# embedded-gw.net
KiCad netlist of a schematic drawn in EAGLE
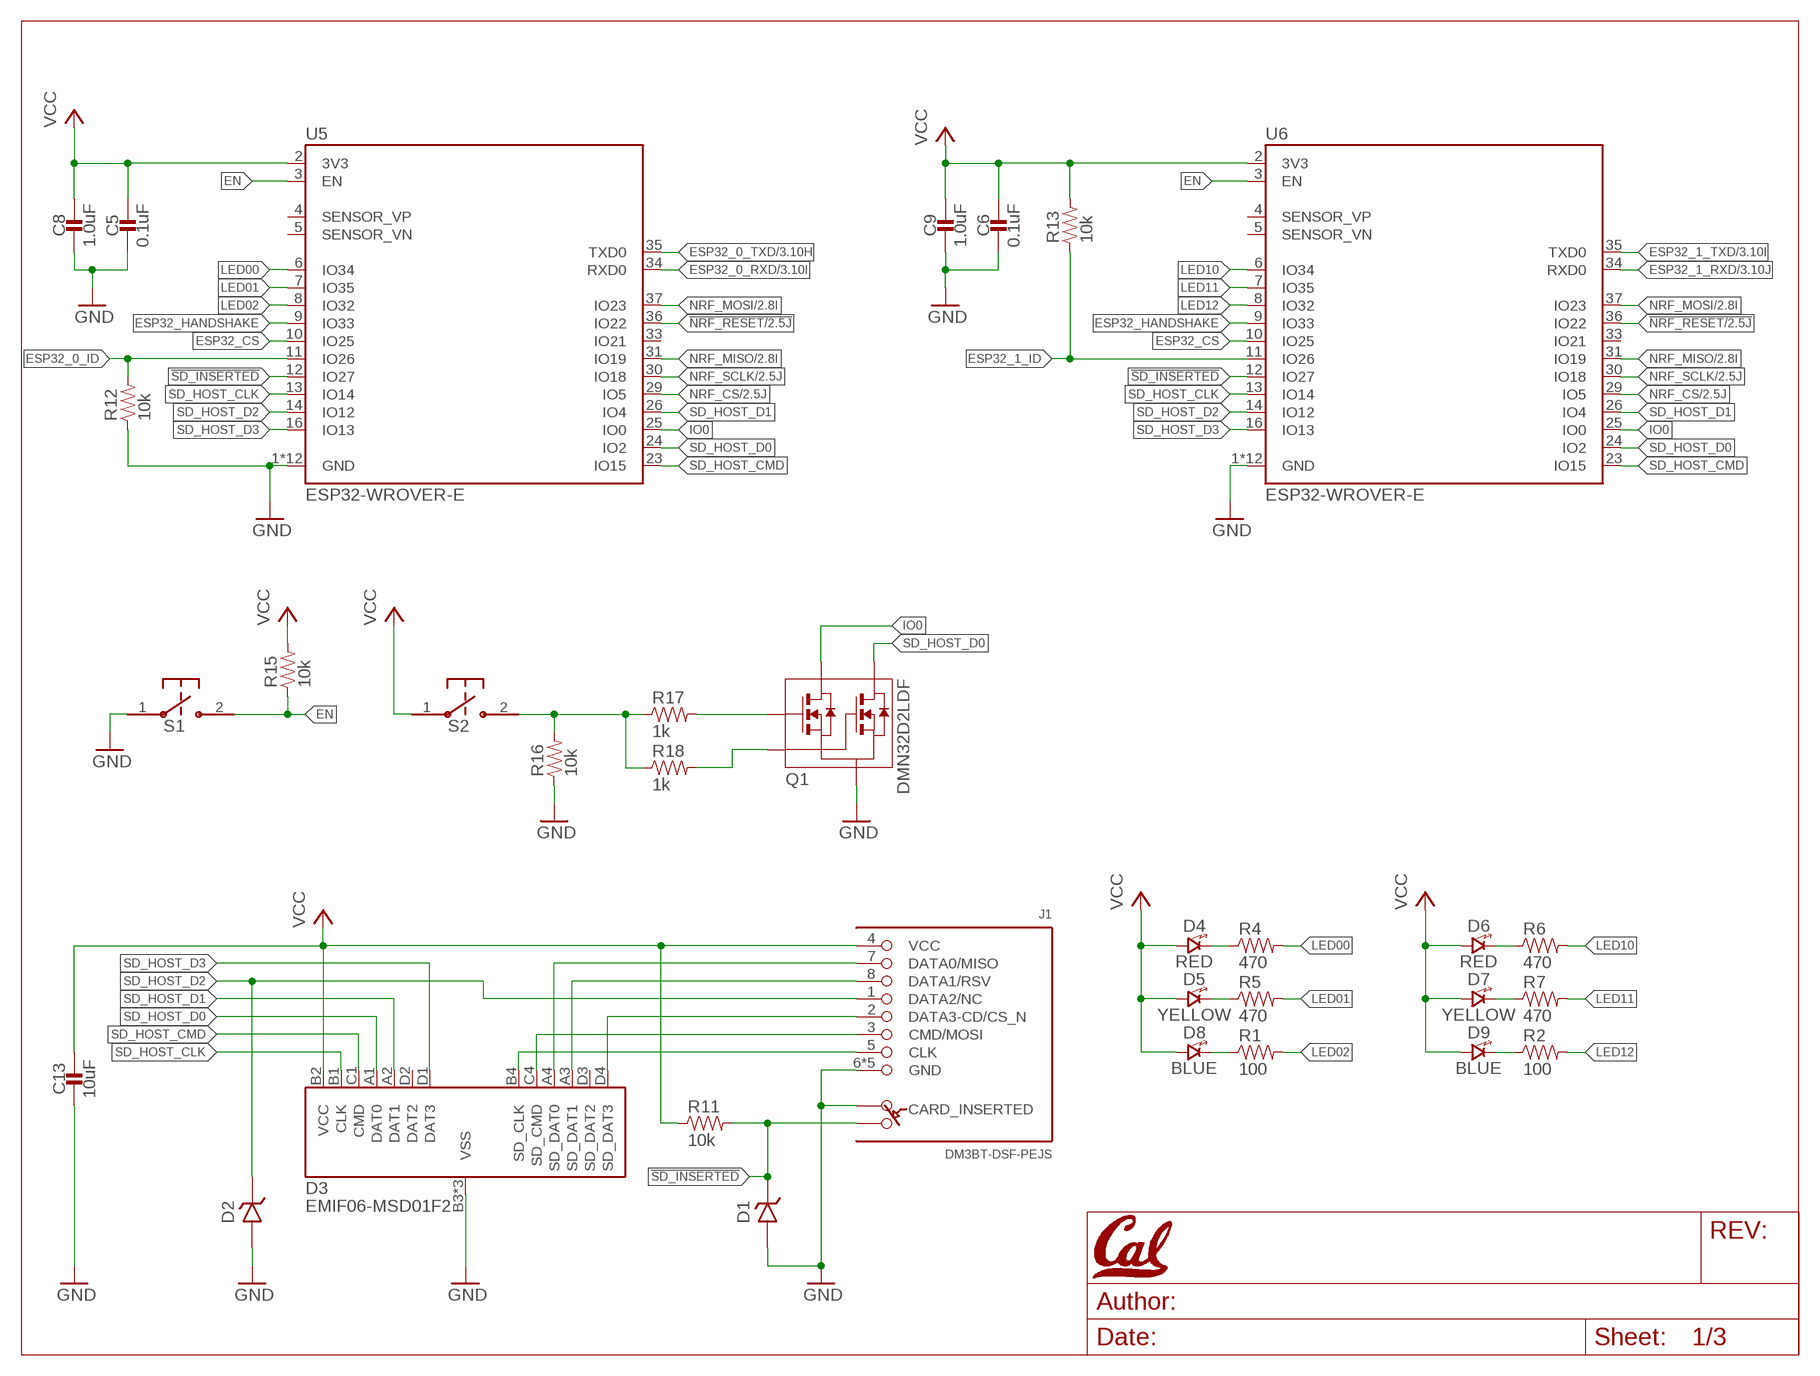
[diagram p0: schematic, sheet 1]
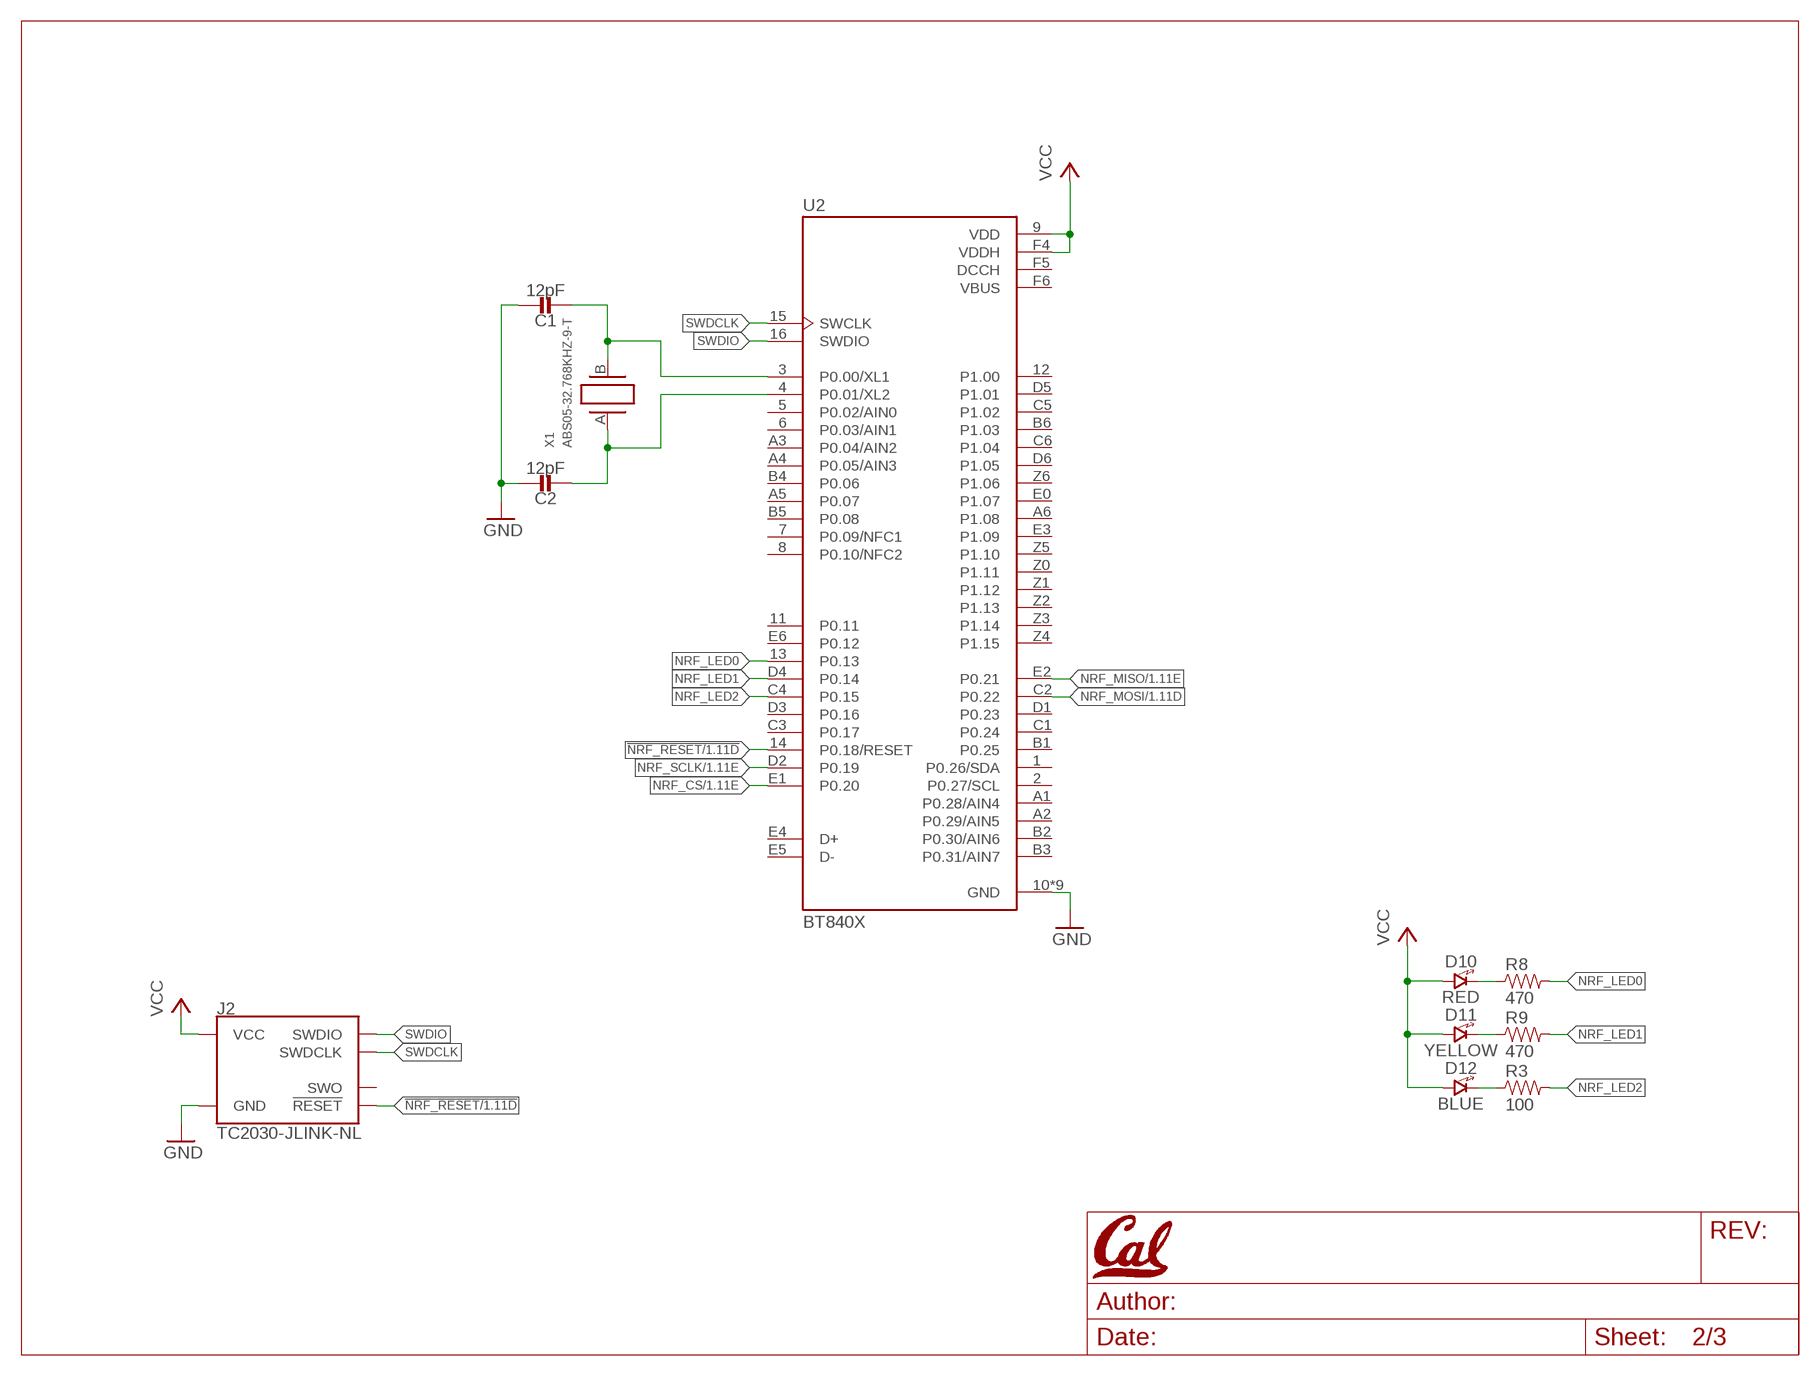
[diagram p1: schematic, sheet 2]
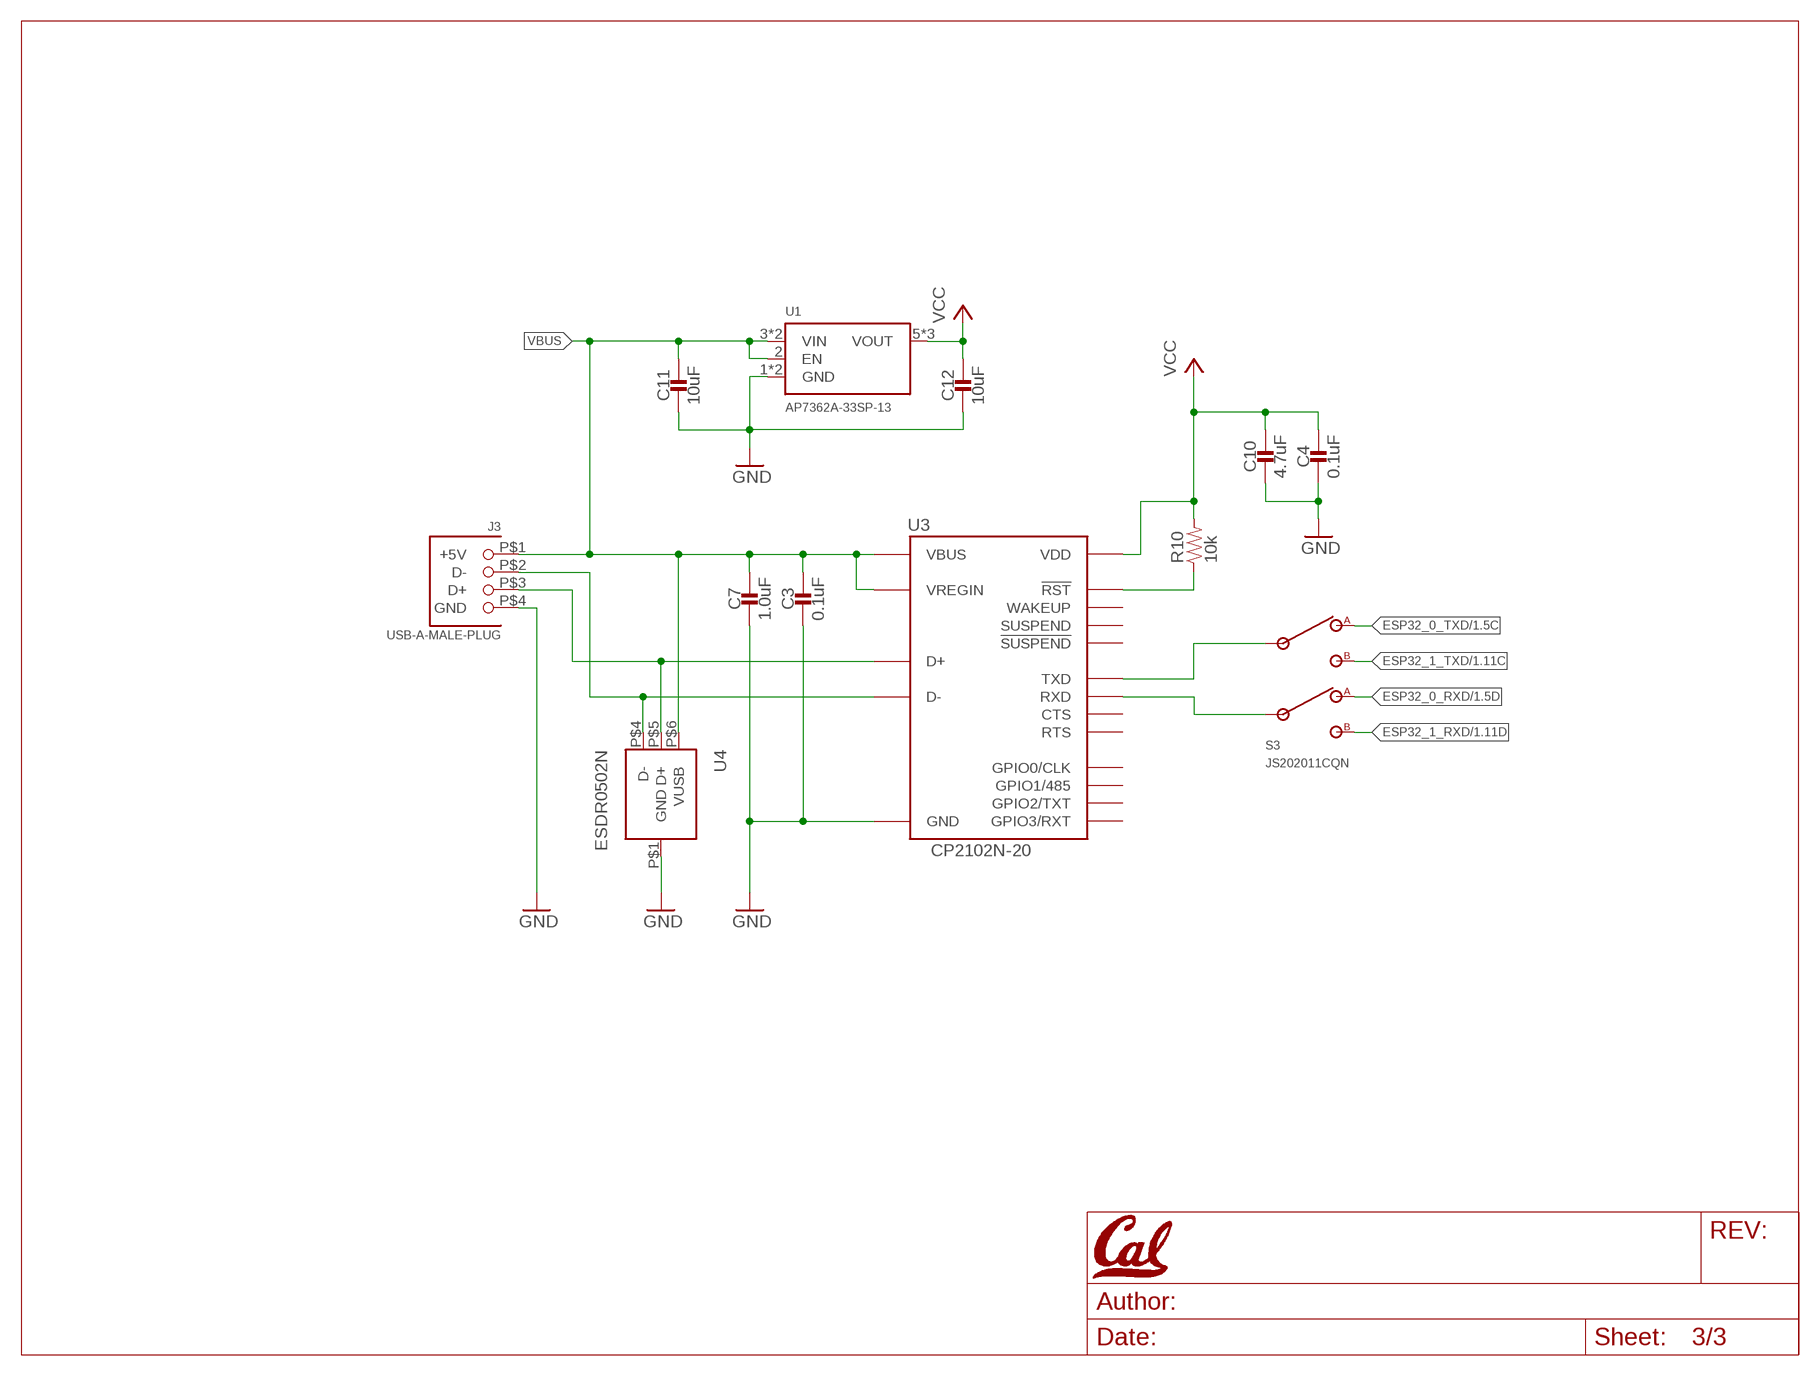
[diagram p2: schematic, sheet 3]

(export (version "E")
  (design (tool "Eeschema 10.0.6"))
  (components
    (comp (ref "C3")
      (value "0.1uF")
      (footprint "eagle-import:0402_CAP")
      (fields (field (name "MPN") "CL05B104KQ5NNNC"))
      (libsource (lib "eagle-import") (part "CAPACITOR0402_CAP"))
    )
    (comp (ref "C4")
      (value "0.1uF")
      (footprint "eagle-import:0402_CAP")
      (fields (field (name "MPN") "CL05B104KQ5NNNC"))
      (libsource (lib "eagle-import") (part "CAPACITOR0402_CAP"))
    )
    (comp (ref "C7")
      (value "1.0uF")
      (footprint "eagle-import:0402_CAP")
      (fields (field (name "MPN") "CL05A105KQ5NNNC"))
      (libsource (lib "eagle-import") (part "CAPACITOR0402_CAP"))
    )
    (comp (ref "C10")
      (value "4.7uF")
      (footprint "eagle-import:0603_CAP")
      (fields (field (name "MPN") "CL10A475KQ8NNNC"))
      (libsource (lib "eagle-import") (part "CAPACITOR0603_CAP"))
    )
    (comp (ref "C11")
      (value "10uF")
      (footprint "eagle-import:0805_CAP")
      (fields (field (name "MPN") "CL21A106KQCLNNC"))
      (libsource (lib "eagle-import") (part "CAPACITOR0805_CAP"))
    )
    (comp (ref "C12")
      (value "10uF")
      (footprint "eagle-import:0805_CAP")
      (fields (field (name "MPN") "CL21A106KQCLNNC"))
      (libsource (lib "eagle-import") (part "CAPACITOR0805_CAP"))
    )
    (comp (ref "J3")
      (value "USB-A-MALE-PLUG")
      (footprint "eagle-import:USB_A_MALE_PLUG_CUI_UP2-AH")
      (fields (field (name "MANUFACTURER") "CUI") (field (name "MPN") "UP2-AH-1-TH"))
      (libsource (lib "eagle-import") (part "USB-A-MALE-PLUG"))
    )
    (comp (ref "R10")
      (value "10k")
      (footprint "eagle-import:0402_RES")
      (fields (field (name "MPN") "RMCF0402JT10K0"))
      (libsource (lib "eagle-import") (part "RESISTOR0402_RES"))
    )
    (comp (ref "S3")
      (value "JS202011CQN")
      (footprint "eagle-import:JS202011CQN")
      (fields (field (name "MANUFACTURER") "C&K"))
      (libsource (lib "eagle-import") (part "JS202011CQN"))
    )
    (comp (ref "U1")
      (value "AP7362A-33SP-13")
      (footprint "eagle-import:SO-8EP")
      (fields (field (name "MANUFACTURER") "Diodes Incorporated") (field (name "MPN") "AP7362A-33SP-13 "))
      (libsource (lib "eagle-import") (part "AP7362A-33SP-13"))
    )
    (comp (ref "U3")
      (value "CP2102N-20")
      (footprint "eagle-import:QFN-20-3MM")
      (fields (field (name "MANUFACTURER") "SiLabs") (field (name "MPN") "CP2102N-A01-GQFN20"))
      (libsource (lib "eagle-import") (part "CP2102N-20"))
    )
    (comp (ref "U4")
      (value "ESDR0502N")
      (footprint "eagle-import:UDFN-6")
      (fields (field (name "MPN") "ESDR0502NMUTBG"))
      (libsource (lib "eagle-import") (part "ESDR0502N"))
    )
    (comp (ref "C5")
      (value "0.1uF")
      (footprint "eagle-import:0402_CAP")
      (fields (field (name "MPN") "CL05B104KQ5NNNC"))
      (libsource (lib "eagle-import") (part "CAPACITOR0402_CAP"))
    )
    (comp (ref "C6")
      (value "0.1uF")
      (footprint "eagle-import:0402_CAP")
      (fields (field (name "MPN") "CL05B104KQ5NNNC"))
      (libsource (lib "eagle-import") (part "CAPACITOR0402_CAP"))
    )
    (comp (ref "C8")
      (value "1.0uF")
      (footprint "eagle-import:0402_CAP")
      (fields (field (name "MPN") "CL05A105KQ5NNNC"))
      (libsource (lib "eagle-import") (part "CAPACITOR0402_CAP"))
    )
    (comp (ref "C9")
      (value "1.0uF")
      (footprint "eagle-import:0402_CAP")
      (fields (field (name "MPN") "CL05A105KQ5NNNC"))
      (libsource (lib "eagle-import") (part "CAPACITOR0402_CAP"))
    )
    (comp (ref "C13")
      (value "10uF")
      (footprint "eagle-import:0805_CAP")
      (fields (field (name "MPN") "CL21A106KQCLNNC"))
      (libsource (lib "eagle-import") (part "CAPACITOR0805_CAP"))
    )
    (comp (ref "D1")
      (value "DIODE_ZENER0201")
      (footprint "eagle-import:0201_DIODE")
      (fields (field (name "MPN") "ESD7381MUT5G"))
      (libsource (lib "eagle-import") (part "DIODE_ZENER0201"))
    )
    (comp (ref "D2")
      (value "DIODE_ZENER0201")
      (footprint "eagle-import:0201_DIODE")
      (fields (field (name "MPN") "ESD7381MUT5G"))
      (libsource (lib "eagle-import") (part "DIODE_ZENER0201"))
    )
    (comp (ref "D3")
      (value "EMIF06-MSD01F2")
      (footprint "eagle-import:BGA16C50P4X4_192X192X65N")
      (fields (field (name "MANUFACTURER") "STMicroelectronics"))
      (libsource (lib "eagle-import") (part "EMIF06-MSD01F2"))
    )
    (comp (ref "D4")
      (value "RED")
      (footprint "eagle-import:LED-0603")
      (fields (field (name "MPN") "LTST-C193KRKT-5A"))
      (libsource (lib "eagle-import") (part "LED0603"))
    )
    (comp (ref "D5")
      (value "YELLOW")
      (footprint "eagle-import:LED-0603")
      (fields (field (name "MPN") "LTST-C193KSKT-5A"))
      (libsource (lib "eagle-import") (part "LED0603"))
    )
    (comp (ref "D6")
      (value "RED")
      (footprint "eagle-import:LED-0603")
      (fields (field (name "MPN") "LTST-C193KRKT-5A"))
      (libsource (lib "eagle-import") (part "LED0603"))
    )
    (comp (ref "D7")
      (value "YELLOW")
      (footprint "eagle-import:LED-0603")
      (fields (field (name "MPN") "LTST-C193KSKT-5A"))
      (libsource (lib "eagle-import") (part "LED0603"))
    )
    (comp (ref "D8")
      (value "BLUE")
      (footprint "eagle-import:LED-0603")
      (fields (field (name "MPN") "LTST-C193TBKT-5A"))
      (libsource (lib "eagle-import") (part "LED0603"))
    )
    (comp (ref "D9")
      (value "BLUE")
      (footprint "eagle-import:LED-0603")
      (fields (field (name "MPN") "LTST-C193TBKT-5A"))
      (libsource (lib "eagle-import") (part "LED0603"))
    )
    (comp (ref "J1")
      (value "DM3BT-DSF-PEJS")
      (footprint "eagle-import:HRS_DM3BT-DSF-PEJS")
      (fields (field (name "MANUFACTURER") "Hirose Connector"))
      (libsource (lib "eagle-import") (part "DM3BT-DSF-PEJS"))
    )
    (comp (ref "Q1")
      (value "DMN32D2LDF")
      (footprint "eagle-import:SOT353")
      (fields (field (name "MANUFACTURER") "Diodes Incorporated") (field (name "MPN") "DMN32D2LDF-7"))
      (libsource (lib "eagle-import") (part "DMN32D2LDF"))
    )
    (comp (ref "R1")
      (value "100")
      (footprint "eagle-import:0402_RES")
      (fields (field (name "MPN") "RC0402JR-07100RL"))
      (libsource (lib "eagle-import") (part "RESISTOR0402_RES"))
    )
    (comp (ref "R2")
      (value "100")
      (footprint "eagle-import:0402_RES")
      (fields (field (name "MPN") "RC0402JR-07100RL"))
      (libsource (lib "eagle-import") (part "RESISTOR0402_RES"))
    )
    (comp (ref "R4")
      (value "470")
      (footprint "eagle-import:0402_RES")
      (fields (field (name "MPN") "RC0402FR-07470RL"))
      (libsource (lib "eagle-import") (part "RESISTOR0402_RES"))
    )
    (comp (ref "R5")
      (value "470")
      (footprint "eagle-import:0402_RES")
      (fields (field (name "MPN") "RC0402FR-07470RL"))
      (libsource (lib "eagle-import") (part "RESISTOR0402_RES"))
    )
    (comp (ref "R6")
      (value "470")
      (footprint "eagle-import:0402_RES")
      (fields (field (name "MPN") "RC0402FR-07470RL"))
      (libsource (lib "eagle-import") (part "RESISTOR0402_RES"))
    )
    (comp (ref "R7")
      (value "470")
      (footprint "eagle-import:0402_RES")
      (fields (field (name "MPN") "RC0402FR-07470RL"))
      (libsource (lib "eagle-import") (part "RESISTOR0402_RES"))
    )
    (comp (ref "R11")
      (value "10k")
      (footprint "eagle-import:0402_RES")
      (fields (field (name "MPN") "RMCF0402JT10K0"))
      (libsource (lib "eagle-import") (part "RESISTOR0402_RES"))
    )
    (comp (ref "R12")
      (value "10k")
      (footprint "eagle-import:0402_RES")
      (fields (field (name "MPN") "RMCF0402JT10K0"))
      (libsource (lib "eagle-import") (part "RESISTOR0402_RES"))
    )
    (comp (ref "R13")
      (value "10k")
      (footprint "eagle-import:0402_RES")
      (fields (field (name "MPN") "RMCF0402JT10K0"))
      (libsource (lib "eagle-import") (part "RESISTOR0402_RES"))
    )
    (comp (ref "R15")
      (value "10k")
      (footprint "eagle-import:0402_RES")
      (fields (field (name "MPN") "RMCF0402JT10K0"))
      (libsource (lib "eagle-import") (part "RESISTOR0402_RES"))
    )
    (comp (ref "R16")
      (value "10k")
      (footprint "eagle-import:0402_RES")
      (fields (field (name "MPN") "RMCF0402JT10K0"))
      (libsource (lib "eagle-import") (part "RESISTOR0402_RES"))
    )
    (comp (ref "R17")
      (value "1k")
      (footprint "eagle-import:0402_RES")
      (fields (field (name "MPN") "RMCF0402JT1K00"))
      (libsource (lib "eagle-import") (part "RESISTOR0402_RES"))
    )
    (comp (ref "R18")
      (value "1k")
      (footprint "eagle-import:0402_RES")
      (fields (field (name "MPN") "RMCF0402JT1K00"))
      (libsource (lib "eagle-import") (part "RESISTOR0402_RES"))
    )
    (comp (ref "S1")
      (value "B3U-1000P")
      (footprint "eagle-import:B3U-1000P")
      (fields (field (name "MANUFACTURER") "Omron"))
      (libsource (lib "eagle-import") (part "B3U-1000P"))
    )
    (comp (ref "S2")
      (value "B3U-1000P")
      (footprint "eagle-import:B3U-1000P")
      (fields (field (name "MANUFACTURER") "Omron"))
      (libsource (lib "eagle-import") (part "B3U-1000P"))
    )
    (comp (ref "U5")
      (value "ESP32-WROVER-E")
      (footprint "eagle-import:ESP32-WROVER-E")
      (fields (field (name "MANUFACTURER") "Espressif Systems") (field (name "MPN") "  ESP32-WROVER-E (8MB)"))
      (libsource (lib "eagle-import") (part "ESP32-WROVER-E"))
    )
    (comp (ref "U6")
      (value "ESP32-WROVER-E")
      (footprint "eagle-import:ESP32-WROVER-E")
      (fields (field (name "MANUFACTURER") "Espressif Systems") (field (name "MPN") "  ESP32-WROVER-E (8MB)"))
      (libsource (lib "eagle-import") (part "ESP32-WROVER-E"))
    )
    (comp (ref "C1")
      (value "12pF")
      (footprint "eagle-import:0402_CAP")
      (fields (field (name "MPN") "GCM1555C1H120GA16D"))
      (libsource (lib "eagle-import") (part "CAPACITOR0402_CAP"))
    )
    (comp (ref "C2")
      (value "12pF")
      (footprint "eagle-import:0402_CAP")
      (fields (field (name "MPN") "GCM1555C1H120GA16D"))
      (libsource (lib "eagle-import") (part "CAPACITOR0402_CAP"))
    )
    (comp (ref "D10")
      (value "RED")
      (footprint "eagle-import:LED-0603")
      (fields (field (name "MPN") "LTST-C193KRKT-5A"))
      (libsource (lib "eagle-import") (part "LED0603"))
    )
    (comp (ref "D11")
      (value "YELLOW")
      (footprint "eagle-import:LED-0603")
      (fields (field (name "MPN") "LTST-C193KSKT-5A"))
      (libsource (lib "eagle-import") (part "LED0603"))
    )
    (comp (ref "D12")
      (value "BLUE")
      (footprint "eagle-import:LED-0603")
      (fields (field (name "MPN") "LTST-C193TBKT-5A"))
      (libsource (lib "eagle-import") (part "LED0603"))
    )
    (comp (ref "J2")
      (value "TC2030-JLINK-NL")
      (footprint "eagle-import:TC2030-IDC-NL")
      (libsource (lib "eagle-import") (part "TC2030-JLINK-NL"))
    )
    (comp (ref "R3")
      (value "100")
      (footprint "eagle-import:0402_RES")
      (fields (field (name "MPN") "RC0402JR-07100RL"))
      (libsource (lib "eagle-import") (part "RESISTOR0402_RES"))
    )
    (comp (ref "R8")
      (value "470")
      (footprint "eagle-import:0402_RES")
      (fields (field (name "MPN") "RC0402FR-07470RL"))
      (libsource (lib "eagle-import") (part "RESISTOR0402_RES"))
    )
    (comp (ref "R9")
      (value "470")
      (footprint "eagle-import:0402_RES")
      (fields (field (name "MPN") "RC0402FR-07470RL"))
      (libsource (lib "eagle-import") (part "RESISTOR0402_RES"))
    )
    (comp (ref "U2")
      (value "BT840X")
      (footprint "eagle-import:XCVR_BT840X")
      (fields (field (name "MANUFACTURER") "Fanstel Corp."))
      (libsource (lib "eagle-import") (part "BT840X"))
    )
    (comp (ref "X1")
      (value "ABS05-32.768KHZ-9-T")
      (footprint "eagle-import:ABS05")
      (fields (field (name "MANUFACTURER") "Abracon"))
      (libsource (lib "eagle-import") (part "ABS05-32.768KHZ-9-T"))
    )
  )
  (nets
    (net (code "1") (name "DCCH") (class "Default")
      (node (ref "U2") (pin "F5") (pinfunction "DCCH_F5") (pintype "power_in"))
    )
    (net (code "2") (name "EN") (class "Default")
      (node (ref "R15") (pin "1") (pinfunction "1_1") (pintype "passive"))
      (node (ref "S1") (pin "2") (pinfunction "P$2_2") (pintype "passive"))
      (node (ref "U5") (pin "3") (pinfunction "EN_3") (pintype "bidirectional"))
      (node (ref "U6") (pin "3") (pinfunction "EN_3") (pintype "bidirectional"))
    )
    (net (code "3") (name "ESP32_0_ID") (class "Default")
      (node (ref "R12") (pin "2") (pinfunction "2_2") (pintype "passive"))
      (node (ref "U5") (pin "11") (pinfunction "IO26_11") (pintype "bidirectional"))
    )
    (net (code "4") (name "ESP32_0_RXD") (class "Default")
      (node (ref "S3") (pin "1") (pinfunction "A2_1") (pintype "bidirectional"))
      (node (ref "U5") (pin "34") (pinfunction "RXD0_34") (pintype "bidirectional"))
    )
    (net (code "5") (name "ESP32_0_TXD") (class "Default")
      (node (ref "S3") (pin "4") (pinfunction "A1_4") (pintype "bidirectional"))
      (node (ref "U5") (pin "35") (pinfunction "TXD0_35") (pintype "bidirectional"))
    )
    (net (code "6") (name "ESP32_1_ID") (class "Default")
      (node (ref "R13") (pin "1") (pinfunction "1_1") (pintype "passive"))
      (node (ref "U6") (pin "11") (pinfunction "IO26_11") (pintype "bidirectional"))
    )
    (net (code "7") (name "ESP32_1_RXD") (class "Default")
      (node (ref "S3") (pin "3") (pinfunction "B2_3") (pintype "bidirectional"))
      (node (ref "U6") (pin "34") (pinfunction "RXD0_34") (pintype "bidirectional"))
    )
    (net (code "8") (name "ESP32_1_TXD") (class "Default")
      (node (ref "S3") (pin "6") (pinfunction "B1_6") (pintype "bidirectional"))
      (node (ref "U6") (pin "35") (pinfunction "TXD0_35") (pintype "bidirectional"))
    )
    (net (code "9") (name "ESP32_CS") (class "Default")
      (node (ref "U5") (pin "10") (pinfunction "IO25_10") (pintype "bidirectional"))
      (node (ref "U6") (pin "10") (pinfunction "IO25_10") (pintype "bidirectional"))
    )
    (net (code "10") (name "ESP32_HANDSHAKE") (class "Default")
      (node (ref "U5") (pin "9") (pinfunction "IO33_9") (pintype "bidirectional"))
      (node (ref "U6") (pin "9") (pinfunction "IO33_9") (pintype "bidirectional"))
    )
    (net (code "11") (name "GND") (class "Default")
      (node (ref "C1") (pin "1") (pinfunction "1_1") (pintype "bidirectional"))
      (node (ref "C10") (pin "2") (pinfunction "2_2") (pintype "bidirectional"))
      (node (ref "C11") (pin "P$2") (pinfunction "2_P$2") (pintype "bidirectional"))
      (node (ref "C12") (pin "P$2") (pinfunction "2_P$2") (pintype "bidirectional"))
      (node (ref "C13") (pin "P$2") (pinfunction "2_P$2") (pintype "bidirectional"))
      (node (ref "C2") (pin "1") (pinfunction "1_1") (pintype "bidirectional"))
      (node (ref "C3") (pin "2") (pinfunction "2_2") (pintype "bidirectional"))
      (node (ref "C4") (pin "2") (pinfunction "2_2") (pintype "bidirectional"))
      (node (ref "C5") (pin "2") (pinfunction "2_2") (pintype "bidirectional"))
      (node (ref "C6") (pin "2") (pinfunction "2_2") (pintype "bidirectional"))
      (node (ref "C7") (pin "2") (pinfunction "2_2") (pintype "bidirectional"))
      (node (ref "C8") (pin "2") (pinfunction "2_2") (pintype "bidirectional"))
      (node (ref "C9") (pin "2") (pinfunction "2_2") (pintype "bidirectional"))
      (node (ref "D1") (pin "P$2") (pinfunction "ANODE_P$2") (pintype "bidirectional"))
      (node (ref "D2") (pin "P$2") (pinfunction "ANODE_P$2") (pintype "bidirectional"))
      (node (ref "D3") (pin "B3") (pinfunction "VSS_B3") (pintype "bidirectional"))
      (node (ref "D3") (pin "C2") (pinfunction "VSS_C2") (pintype "bidirectional"))
      (node (ref "D3") (pin "C3") (pinfunction "VSS_C3") (pintype "bidirectional"))
      (node (ref "J1") (pin "6") (pinfunction "GND_6") (pintype "bidirectional"))
      (node (ref "J1") (pin "S1") (pinfunction "GND_S1") (pintype "bidirectional"))
      (node (ref "J1") (pin "S2") (pinfunction "GND_S2") (pintype "bidirectional"))
      (node (ref "J1") (pin "S3") (pinfunction "GND_S3") (pintype "bidirectional"))
      (node (ref "J1") (pin "S4") (pinfunction "GND_S4") (pintype "bidirectional"))
      (node (ref "J1") (pin "SW-A") (pinfunction "A_SW-A") (pintype "bidirectional"))
      (node (ref "J2") (pin "5") (pinfunction "GND_5") (pintype "bidirectional"))
      (node (ref "J3") (pin "P$4") (pinfunction "GND_P$4") (pintype "bidirectional"))
      (node (ref "Q1") (pin "S") (pinfunction "S_S") (pintype "bidirectional"))
      (node (ref "R12") (pin "1") (pinfunction "1_1") (pintype "passive"))
      (node (ref "R16") (pin "1") (pinfunction "1_1") (pintype "passive"))
      (node (ref "S1") (pin "1") (pinfunction "P$1_1") (pintype "passive"))
      (node (ref "U1") (pin "1") (pinfunction "GND_1") (pintype "bidirectional"))
      (node (ref "U1") (pin "PAD") (pinfunction "GND_PAD") (pintype "bidirectional"))
      (node (ref "U2") (pin "10") (pinfunction "GND_10") (pintype "power_in"))
      (node (ref "U2") (pin "A0") (pinfunction "GND_A0") (pintype "power_in"))
      (node (ref "U2") (pin "B0") (pinfunction "GND_B0") (pintype "power_in"))
      (node (ref "U2") (pin "C0") (pinfunction "GND_C0") (pintype "power_in"))
      (node (ref "U2") (pin "D0") (pinfunction "GND_D0") (pintype "power_in"))
      (node (ref "U2") (pin "F0") (pinfunction "GND_F0") (pintype "power_in"))
      (node (ref "U2") (pin "F1") (pinfunction "GND_F1") (pintype "power_in"))
      (node (ref "U2") (pin "F2") (pinfunction "GND_F2") (pintype "power_in"))
      (node (ref "U2") (pin "F3") (pinfunction "GND_F3") (pintype "power_in"))
      (node (ref "U3") (pin "12") (pinfunction "GND_12") (pintype "bidirectional"))
      (node (ref "U3") (pin "3") (pinfunction "GND_3") (pintype "bidirectional"))
      (node (ref "U3") (pin "P$1") (pinfunction "GND_P$1") (pintype "bidirectional"))
      (node (ref "U4") (pin "P$1") (pinfunction "GND_P$1") (pintype "bidirectional"))
      (node (ref "U5") (pin "1") (pinfunction "GND_1") (pintype "bidirectional"))
      (node (ref "U5") (pin "15") (pinfunction "GND_15") (pintype "bidirectional"))
      (node (ref "U5") (pin "38") (pinfunction "GND_38") (pintype "bidirectional"))
      (node (ref "U5") (pin "GND1") (pinfunction "GND_GND1") (pintype "bidirectional"))
      (node (ref "U5") (pin "GND2") (pinfunction "GND_GND2") (pintype "bidirectional"))
      (node (ref "U5") (pin "GND3") (pinfunction "GND_GND3") (pintype "bidirectional"))
      (node (ref "U5") (pin "GND4") (pinfunction "GND_GND4") (pintype "bidirectional"))
      (node (ref "U5") (pin "GND5") (pinfunction "GND_GND5") (pintype "bidirectional"))
      (node (ref "U5") (pin "GND6") (pinfunction "GND_GND6") (pintype "bidirectional"))
      (node (ref "U5") (pin "GND7") (pinfunction "GND_GND7") (pintype "bidirectional"))
      (node (ref "U5") (pin "GND8") (pinfunction "GND_GND8") (pintype "bidirectional"))
      (node (ref "U5") (pin "GND9") (pinfunction "GND_GND9") (pintype "bidirectional"))
      (node (ref "U6") (pin "1") (pinfunction "GND_1") (pintype "bidirectional"))
      (node (ref "U6") (pin "15") (pinfunction "GND_15") (pintype "bidirectional"))
      (node (ref "U6") (pin "38") (pinfunction "GND_38") (pintype "bidirectional"))
      (node (ref "U6") (pin "GND1") (pinfunction "GND_GND1") (pintype "bidirectional"))
      (node (ref "U6") (pin "GND2") (pinfunction "GND_GND2") (pintype "bidirectional"))
      (node (ref "U6") (pin "GND3") (pinfunction "GND_GND3") (pintype "bidirectional"))
      (node (ref "U6") (pin "GND4") (pinfunction "GND_GND4") (pintype "bidirectional"))
      (node (ref "U6") (pin "GND5") (pinfunction "GND_GND5") (pintype "bidirectional"))
      (node (ref "U6") (pin "GND6") (pinfunction "GND_GND6") (pintype "bidirectional"))
      (node (ref "U6") (pin "GND7") (pinfunction "GND_GND7") (pintype "bidirectional"))
      (node (ref "U6") (pin "GND8") (pinfunction "GND_GND8") (pintype "bidirectional"))
      (node (ref "U6") (pin "GND9") (pinfunction "GND_GND9") (pintype "bidirectional"))
    )
    (net (code "12") (name "IO0") (class "Default")
      (node (ref "Q1") (pin "D1") (pinfunction "D1_D1") (pintype "bidirectional"))
      (node (ref "U5") (pin "25") (pinfunction "IO0_25") (pintype "bidirectional"))
      (node (ref "U6") (pin "25") (pinfunction "IO0_25") (pintype "bidirectional"))
    )
    (net (code "13") (name "LED00") (class "Default")
      (node (ref "R4") (pin "2") (pinfunction "2_2") (pintype "passive"))
      (node (ref "U5") (pin "6") (pinfunction "IO34_6") (pintype "bidirectional"))
    )
    (net (code "14") (name "LED01") (class "Default")
      (node (ref "R5") (pin "2") (pinfunction "2_2") (pintype "passive"))
      (node (ref "U5") (pin "7") (pinfunction "IO35_7") (pintype "bidirectional"))
    )
    (net (code "15") (name "LED02") (class "Default")
      (node (ref "R1") (pin "2") (pinfunction "2_2") (pintype "passive"))
      (node (ref "U5") (pin "8") (pinfunction "IO32_8") (pintype "bidirectional"))
    )
    (net (code "16") (name "LED10") (class "Default")
      (node (ref "R6") (pin "2") (pinfunction "2_2") (pintype "passive"))
      (node (ref "U6") (pin "6") (pinfunction "IO34_6") (pintype "bidirectional"))
    )
    (net (code "17") (name "LED11") (class "Default")
      (node (ref "R7") (pin "2") (pinfunction "2_2") (pintype "passive"))
      (node (ref "U6") (pin "7") (pinfunction "IO35_7") (pintype "bidirectional"))
    )
    (net (code "18") (name "LED12") (class "Default")
      (node (ref "R2") (pin "2") (pinfunction "2_2") (pintype "passive"))
      (node (ref "U6") (pin "8") (pinfunction "IO32_8") (pintype "bidirectional"))
    )
    (net (code "19") (name "NRF_CS") (class "Default")
      (node (ref "U2") (pin "E1") (pinfunction "P0.20_E1") (pintype "bidirectional"))
      (node (ref "U5") (pin "29") (pinfunction "IO5_29") (pintype "bidirectional"))
      (node (ref "U6") (pin "29") (pinfunction "IO5_29") (pintype "bidirectional"))
    )
    (net (code "20") (name "NRF_LED0") (class "Default")
      (node (ref "R8") (pin "2") (pinfunction "2_2") (pintype "passive"))
      (node (ref "U2") (pin "13") (pinfunction "P0.13_13") (pintype "bidirectional"))
    )
    (net (code "21") (name "NRF_LED1") (class "Default")
      (node (ref "R9") (pin "2") (pinfunction "2_2") (pintype "passive"))
      (node (ref "U2") (pin "D4") (pinfunction "P0.14_D4") (pintype "bidirectional"))
    )
    (net (code "22") (name "NRF_LED2") (class "Default")
      (node (ref "R3") (pin "2") (pinfunction "2_2") (pintype "passive"))
      (node (ref "U2") (pin "C4") (pinfunction "P0.15_C4") (pintype "bidirectional"))
    )
    (net (code "23") (name "NRF_MISO") (class "Default")
      (node (ref "U2") (pin "E2") (pinfunction "P0.21_E2") (pintype "bidirectional"))
      (node (ref "U5") (pin "31") (pinfunction "IO19_31") (pintype "bidirectional"))
      (node (ref "U6") (pin "31") (pinfunction "IO19_31") (pintype "bidirectional"))
    )
    (net (code "24") (name "NRF_MOSI") (class "Default")
      (node (ref "U2") (pin "C2") (pinfunction "P0.22_C2") (pintype "bidirectional"))
      (node (ref "U5") (pin "37") (pinfunction "IO23_37") (pintype "bidirectional"))
      (node (ref "U6") (pin "37") (pinfunction "IO23_37") (pintype "bidirectional"))
    )
    (net (code "25") (name "NRF_SCLK") (class "Default")
      (node (ref "U2") (pin "D2") (pinfunction "P0.19_D2") (pintype "bidirectional"))
      (node (ref "U5") (pin "30") (pinfunction "IO18_30") (pintype "bidirectional"))
      (node (ref "U6") (pin "30") (pinfunction "IO18_30") (pintype "bidirectional"))
    )
    (net (code "26") (name "Net-(D3-SD_CLK)") (class "Default")
      (node (ref "D3") (pin "B4") (pinfunction "SD_CLK_B4") (pintype "bidirectional"))
      (node (ref "J1") (pin "5") (pinfunction "CLK_5") (pintype "bidirectional"))
    )
    (net (code "27") (name "Net-(D3-SD_CMD)") (class "Default")
      (node (ref "D3") (pin "C4") (pinfunction "SD_CMD_C4") (pintype "bidirectional"))
      (node (ref "J1") (pin "3") (pinfunction "CMD/MOSI_3") (pintype "bidirectional"))
    )
    (net (code "28") (name "Net-(D3-SD_DAT0)") (class "Default")
      (node (ref "D3") (pin "A4") (pinfunction "SD_DAT0_A4") (pintype "bidirectional"))
      (node (ref "J1") (pin "7") (pinfunction "DATA0/MISO_7") (pintype "bidirectional"))
    )
    (net (code "29") (name "Net-(D3-SD_DAT1)") (class "Default")
      (node (ref "D3") (pin "A3") (pinfunction "SD_DAT1_A3") (pintype "bidirectional"))
      (node (ref "J1") (pin "8") (pinfunction "DATA1/RSV_8") (pintype "bidirectional"))
    )
    (net (code "30") (name "Net-(D3-SD_DAT3)") (class "Default")
      (node (ref "D3") (pin "D4") (pinfunction "SD_DAT3_D4") (pintype "bidirectional"))
      (node (ref "J1") (pin "2") (pinfunction "DATA3-CD/CS_N_2") (pintype "bidirectional"))
    )
    (net (code "31") (name "Net-(D4-CATHODE)") (class "Default")
      (node (ref "D4") (pin "C") (pinfunction "CATHODE_C") (pintype "bidirectional"))
      (node (ref "R4") (pin "1") (pinfunction "1_1") (pintype "passive"))
    )
    (net (code "32") (name "Net-(D5-CATHODE)") (class "Default")
      (node (ref "D5") (pin "C") (pinfunction "CATHODE_C") (pintype "bidirectional"))
      (node (ref "R5") (pin "1") (pinfunction "1_1") (pintype "passive"))
    )
    (net (code "33") (name "Net-(D6-CATHODE)") (class "Default")
      (node (ref "D6") (pin "C") (pinfunction "CATHODE_C") (pintype "bidirectional"))
      (node (ref "R6") (pin "1") (pinfunction "1_1") (pintype "passive"))
    )
    (net (code "34") (name "Net-(D7-CATHODE)") (class "Default")
      (node (ref "D7") (pin "C") (pinfunction "CATHODE_C") (pintype "bidirectional"))
      (node (ref "R7") (pin "1") (pinfunction "1_1") (pintype "passive"))
    )
    (net (code "35") (name "Net-(D8-CATHODE)") (class "Default")
      (node (ref "D8") (pin "C") (pinfunction "CATHODE_C") (pintype "bidirectional"))
      (node (ref "R1") (pin "1") (pinfunction "1_1") (pintype "passive"))
    )
    (net (code "36") (name "Net-(D9-CATHODE)") (class "Default")
      (node (ref "D9") (pin "C") (pinfunction "CATHODE_C") (pintype "bidirectional"))
      (node (ref "R2") (pin "1") (pinfunction "1_1") (pintype "passive"))
    )
    (net (code "37") (name "Net-(D10-CATHODE)") (class "Default")
      (node (ref "D10") (pin "C") (pinfunction "CATHODE_C") (pintype "bidirectional"))
      (node (ref "R8") (pin "1") (pinfunction "1_1") (pintype "passive"))
    )
    (net (code "38") (name "Net-(D11-CATHODE)") (class "Default")
      (node (ref "D11") (pin "C") (pinfunction "CATHODE_C") (pintype "bidirectional"))
      (node (ref "R9") (pin "1") (pinfunction "1_1") (pintype "passive"))
    )
    (net (code "39") (name "Net-(D12-CATHODE)") (class "Default")
      (node (ref "D12") (pin "C") (pinfunction "CATHODE_C") (pintype "bidirectional"))
      (node (ref "R3") (pin "1") (pinfunction "1_1") (pintype "passive"))
    )
    (net (code "40") (name "Net-(J3-D+)") (class "Default")
      (node (ref "J3") (pin "P$3") (pinfunction "D+_P$3") (pintype "bidirectional"))
      (node (ref "U3") (pin "4") (pinfunction "D+_4") (pintype "bidirectional"))
      (node (ref "U4") (pin "P$5") (pinfunction "D+_P$5") (pintype "bidirectional"))
    )
    (net (code "41") (name "Net-(J3-D-)") (class "Default")
      (node (ref "J3") (pin "P$2") (pinfunction "D-_P$2") (pintype "bidirectional"))
      (node (ref "U3") (pin "5") (pinfunction "D-_5") (pintype "bidirectional"))
      (node (ref "U4") (pin "P$4") (pinfunction "D-_P$4") (pintype "bidirectional"))
    )
    (net (code "42") (name "Net-(Q1-PadG1)") (class "Default")
      (node (ref "Q1") (pin "G1") (pinfunction "G1_G1") (pintype "input"))
      (node (ref "R17") (pin "2") (pinfunction "2_2") (pintype "passive"))
    )
    (net (code "43") (name "Net-(Q1-PadG2)") (class "Default")
      (node (ref "Q1") (pin "G2") (pinfunction "G2_G2") (pintype "input"))
      (node (ref "R18") (pin "2") (pinfunction "2_2") (pintype "passive"))
    )
    (net (code "44") (name "Net-(S2-P$2)") (class "Default")
      (node (ref "R16") (pin "2") (pinfunction "2_2") (pintype "passive"))
      (node (ref "R17") (pin "1") (pinfunction "1_1") (pintype "passive"))
      (node (ref "R18") (pin "1") (pinfunction "1_1") (pintype "passive"))
      (node (ref "S2") (pin "2") (pinfunction "P$2_2") (pintype "passive"))
    )
    (net (code "45") (name "Net-(S3-I1)") (class "Default")
      (node (ref "S3") (pin "5") (pinfunction "I1_5") (pintype "bidirectional"))
      (node (ref "U3") (pin "18") (pinfunction "TXD_18") (pintype "bidirectional"))
    )
    (net (code "46") (name "Net-(S3-I2)") (class "Default")
      (node (ref "S3") (pin "2") (pinfunction "I2_2") (pintype "bidirectional"))
      (node (ref "U3") (pin "17") (pinfunction "RXD_17") (pintype "bidirectional"))
    )
    (net (code "47") (name "Net-(U2-P0.00{slash}XL1)") (class "Default")
      (node (ref "C1") (pin "2") (pinfunction "2_2") (pintype "bidirectional"))
      (node (ref "U2") (pin "3") (pinfunction "P0.00/XL1_3") (pintype "bidirectional"))
      (node (ref "X1") (pin "B") (pinfunction "2_B") (pintype "bidirectional"))
    )
    (net (code "48") (name "Net-(U2-P0.01{slash}XL2)") (class "Default")
      (node (ref "C2") (pin "2") (pinfunction "2_2") (pintype "bidirectional"))
      (node (ref "U2") (pin "4") (pinfunction "P0.01/XL2_4") (pintype "bidirectional"))
      (node (ref "X1") (pin "A") (pinfunction "1_A") (pintype "bidirectional"))
    )
    (net (code "49") (name "Net-(U3-~{RST})") (class "Default")
      (node (ref "R10") (pin "1") (pinfunction "1_1") (pintype "passive"))
      (node (ref "U3") (pin "9") (pinfunction "~{RST}_9") (pintype "bidirectional"))
    )
    (net (code "50") (name "SD_HOST_CLK") (class "Default")
      (node (ref "D3") (pin "B1") (pinfunction "CLK_B1") (pintype "bidirectional"))
      (node (ref "U5") (pin "13") (pinfunction "IO14_13") (pintype "bidirectional"))
      (node (ref "U6") (pin "13") (pinfunction "IO14_13") (pintype "bidirectional"))
    )
    (net (code "51") (name "SD_HOST_CMD") (class "Default")
      (node (ref "D3") (pin "C1") (pinfunction "CMD_C1") (pintype "bidirectional"))
      (node (ref "U5") (pin "23") (pinfunction "IO15_23") (pintype "bidirectional"))
      (node (ref "U6") (pin "23") (pinfunction "IO15_23") (pintype "bidirectional"))
    )
    (net (code "52") (name "SD_HOST_D0") (class "Default")
      (node (ref "D3") (pin "A1") (pinfunction "DAT0_A1") (pintype "bidirectional"))
      (node (ref "Q1") (pin "D2") (pinfunction "D2_D2") (pintype "bidirectional"))
      (node (ref "U5") (pin "24") (pinfunction "IO2_24") (pintype "bidirectional"))
      (node (ref "U6") (pin "24") (pinfunction "IO2_24") (pintype "bidirectional"))
    )
    (net (code "53") (name "SD_HOST_D1") (class "Default")
      (node (ref "D3") (pin "A2") (pinfunction "DAT1_A2") (pintype "bidirectional"))
      (node (ref "U5") (pin "26") (pinfunction "IO4_26") (pintype "bidirectional"))
      (node (ref "U6") (pin "26") (pinfunction "IO4_26") (pintype "bidirectional"))
    )
    (net (code "54") (name "SD_HOST_D2") (class "Default")
      (node (ref "D2") (pin "P$1") (pinfunction "CATHODE_P$1") (pintype "bidirectional"))
      (node (ref "J1") (pin "1") (pinfunction "DATA2/NC_1") (pintype "bidirectional"))
      (node (ref "U5") (pin "14") (pinfunction "IO12_14") (pintype "bidirectional"))
      (node (ref "U6") (pin "14") (pinfunction "IO12_14") (pintype "bidirectional"))
    )
    (net (code "55") (name "SD_HOST_D3") (class "Default")
      (node (ref "D3") (pin "D1") (pinfunction "DAT3_D1") (pintype "bidirectional"))
      (node (ref "U5") (pin "16") (pinfunction "IO13_16") (pintype "bidirectional"))
      (node (ref "U6") (pin "16") (pinfunction "IO13_16") (pintype "bidirectional"))
    )
    (net (code "56") (name "SWDCLK") (class "Default")
      (node (ref "J2") (pin "4") (pinfunction "SWDCLK_4") (pintype "bidirectional"))
      (node (ref "U2") (pin "15") (pinfunction "SWCLK_15") (pintype "input"))
    )
    (net (code "57") (name "SWDIO") (class "Default")
      (node (ref "J2") (pin "2") (pinfunction "SWDIO_2") (pintype "bidirectional"))
      (node (ref "U2") (pin "16") (pinfunction "SWDIO_16") (pintype "bidirectional"))
    )
    (net (code "58") (name "VBUS") (class "Default")
      (node (ref "C11") (pin "P$1") (pinfunction "1_P$1") (pintype "bidirectional"))
      (node (ref "C3") (pin "1") (pinfunction "1_1") (pintype "bidirectional"))
      (node (ref "C7") (pin "1") (pinfunction "1_1") (pintype "bidirectional"))
      (node (ref "J3") (pin "P$1") (pinfunction "+5V_P$1") (pintype "bidirectional"))
      (node (ref "U1") (pin "2") (pinfunction "EN_2") (pintype "bidirectional"))
      (node (ref "U1") (pin "3") (pinfunction "VIN_3") (pintype "bidirectional"))
      (node (ref "U1") (pin "4") (pinfunction "VIN_4") (pintype "bidirectional"))
      (node (ref "U3") (pin "7") (pinfunction "VREGIN_7") (pintype "bidirectional"))
      (node (ref "U3") (pin "8") (pinfunction "VBUS_8") (pintype "bidirectional"))
      (node (ref "U4") (pin "P$6") (pinfunction "VUSB_P$6") (pintype "bidirectional"))
    )
    (net (code "59") (name "VCC") (class "Default")
      (node (ref "C10") (pin "1") (pinfunction "1_1") (pintype "bidirectional"))
      (node (ref "C12") (pin "P$1") (pinfunction "1_P$1") (pintype "bidirectional"))
      (node (ref "C13") (pin "P$1") (pinfunction "1_P$1") (pintype "bidirectional"))
      (node (ref "C4") (pin "1") (pinfunction "1_1") (pintype "bidirectional"))
      (node (ref "C5") (pin "1") (pinfunction "1_1") (pintype "bidirectional"))
      (node (ref "C6") (pin "1") (pinfunction "1_1") (pintype "bidirectional"))
      (node (ref "C8") (pin "1") (pinfunction "1_1") (pintype "bidirectional"))
      (node (ref "C9") (pin "1") (pinfunction "1_1") (pintype "bidirectional"))
      (node (ref "D10") (pin "A") (pinfunction "ANODE_A") (pintype "bidirectional"))
      (node (ref "D11") (pin "A") (pinfunction "ANODE_A") (pintype "bidirectional"))
      (node (ref "D12") (pin "A") (pinfunction "ANODE_A") (pintype "bidirectional"))
      (node (ref "D3") (pin "B2") (pinfunction "VCC_B2") (pintype "bidirectional"))
      (node (ref "D4") (pin "A") (pinfunction "ANODE_A") (pintype "bidirectional"))
      (node (ref "D5") (pin "A") (pinfunction "ANODE_A") (pintype "bidirectional"))
      (node (ref "D6") (pin "A") (pinfunction "ANODE_A") (pintype "bidirectional"))
      (node (ref "D7") (pin "A") (pinfunction "ANODE_A") (pintype "bidirectional"))
      (node (ref "D8") (pin "A") (pinfunction "ANODE_A") (pintype "bidirectional"))
      (node (ref "D9") (pin "A") (pinfunction "ANODE_A") (pintype "bidirectional"))
      (node (ref "J1") (pin "4") (pinfunction "VCC_4") (pintype "bidirectional"))
      (node (ref "J2") (pin "1") (pinfunction "VCC_1") (pintype "bidirectional"))
      (node (ref "R10") (pin "2") (pinfunction "2_2") (pintype "passive"))
      (node (ref "R11") (pin "1") (pinfunction "1_1") (pintype "passive"))
      (node (ref "R13") (pin "2") (pinfunction "2_2") (pintype "passive"))
      (node (ref "R15") (pin "2") (pinfunction "2_2") (pintype "passive"))
      (node (ref "S2") (pin "1") (pinfunction "P$1_1") (pintype "passive"))
      (node (ref "U1") (pin "5") (pinfunction "VOUT_5") (pintype "bidirectional"))
      (node (ref "U1") (pin "6") (pinfunction "VOUT_6") (pintype "bidirectional"))
      (node (ref "U1") (pin "7") (pinfunction "VOUT_7") (pintype "bidirectional"))
      (node (ref "U2") (pin "9") (pinfunction "VDD_9") (pintype "power_in"))
      (node (ref "U2") (pin "F4") (pinfunction "VDDH_F4") (pintype "power_in"))
      (node (ref "U3") (pin "6") (pinfunction "VDD_6") (pintype "bidirectional"))
      (node (ref "U5") (pin "2") (pinfunction "3V3_2") (pintype "bidirectional"))
      (node (ref "U6") (pin "2") (pinfunction "3V3_2") (pintype "bidirectional"))
    )
    (net (code "60") (name "unconnected-(D3-DAT2-PadD2)") (class "Default")
      (node (ref "D3") (pin "D2") (pinfunction "DAT2_D2") (pintype "bidirectional"))
    )
    (net (code "61") (name "unconnected-(D3-SD_DAT2-PadD3)") (class "Default")
      (node (ref "D3") (pin "D3") (pinfunction "SD_DAT2_D3") (pintype "bidirectional"))
    )
    (net (code "62") (name "unconnected-(J2-SWO-Pad6)") (class "Default")
      (node (ref "J2") (pin "6") (pinfunction "SWO_6") (pintype "bidirectional"))
    )
    (net (code "63") (name "unconnected-(U2-D+-PadE4)") (class "Default")
      (node (ref "U2") (pin "E4") (pinfunction "D+_E4") (pintype "bidirectional"))
    )
    (net (code "64") (name "unconnected-(U2-D--PadE5)") (class "Default")
      (node (ref "U2") (pin "E5") (pinfunction "D-_E5") (pintype "bidirectional"))
    )
    (net (code "65") (name "unconnected-(U2-P0.02{slash}AIN0-Pad5)") (class "Default")
      (node (ref "U2") (pin "5") (pinfunction "P0.02/AIN0_5") (pintype "bidirectional"))
    )
    (net (code "66") (name "unconnected-(U2-P0.03{slash}AIN1-Pad6)") (class "Default")
      (node (ref "U2") (pin "6") (pinfunction "P0.03/AIN1_6") (pintype "bidirectional"))
    )
    (net (code "67") (name "unconnected-(U2-P0.04{slash}AIN2-PadA3)") (class "Default")
      (node (ref "U2") (pin "A3") (pinfunction "P0.04/AIN2_A3") (pintype "bidirectional"))
    )
    (net (code "68") (name "unconnected-(U2-P0.05{slash}AIN3-PadA4)") (class "Default")
      (node (ref "U2") (pin "A4") (pinfunction "P0.05/AIN3_A4") (pintype "bidirectional"))
    )
    (net (code "69") (name "unconnected-(U2-P0.06-PadB4)") (class "Default")
      (node (ref "U2") (pin "B4") (pinfunction "P0.06_B4") (pintype "bidirectional"))
    )
    (net (code "70") (name "unconnected-(U2-P0.07-PadA5)") (class "Default")
      (node (ref "U2") (pin "A5") (pinfunction "P0.07_A5") (pintype "bidirectional"))
    )
    (net (code "71") (name "unconnected-(U2-P0.08-PadB5)") (class "Default")
      (node (ref "U2") (pin "B5") (pinfunction "P0.08_B5") (pintype "bidirectional"))
    )
    (net (code "72") (name "unconnected-(U2-P0.09{slash}NFC1-Pad7)") (class "Default")
      (node (ref "U2") (pin "7") (pinfunction "P0.09/NFC1_7") (pintype "bidirectional"))
    )
    (net (code "73") (name "unconnected-(U2-P0.10{slash}NFC2-Pad8)") (class "Default")
      (node (ref "U2") (pin "8") (pinfunction "P0.10/NFC2_8") (pintype "bidirectional"))
    )
    (net (code "74") (name "unconnected-(U2-P0.11-Pad11)") (class "Default")
      (node (ref "U2") (pin "11") (pinfunction "P0.11_11") (pintype "bidirectional"))
    )
    (net (code "75") (name "unconnected-(U2-P0.12-PadE6)") (class "Default")
      (node (ref "U2") (pin "E6") (pinfunction "P0.12_E6") (pintype "bidirectional"))
    )
    (net (code "76") (name "unconnected-(U2-P0.16-PadD3)") (class "Default")
      (node (ref "U2") (pin "D3") (pinfunction "P0.16_D3") (pintype "bidirectional"))
    )
    (net (code "77") (name "unconnected-(U2-P0.17-PadC3)") (class "Default")
      (node (ref "U2") (pin "C3") (pinfunction "P0.17_C3") (pintype "bidirectional"))
    )
    (net (code "78") (name "unconnected-(U2-P0.23-PadD1)") (class "Default")
      (node (ref "U2") (pin "D1") (pinfunction "P0.23_D1") (pintype "bidirectional"))
    )
    (net (code "79") (name "unconnected-(U2-P0.24-PadC1)") (class "Default")
      (node (ref "U2") (pin "C1") (pinfunction "P0.24_C1") (pintype "bidirectional"))
    )
    (net (code "80") (name "unconnected-(U2-P0.25-PadB1)") (class "Default")
      (node (ref "U2") (pin "B1") (pinfunction "P0.25_B1") (pintype "bidirectional"))
    )
    (net (code "81") (name "unconnected-(U2-P0.26{slash}SDA-Pad1)") (class "Default")
      (node (ref "U2") (pin "1") (pinfunction "P0.26/SDA_1") (pintype "bidirectional"))
    )
    (net (code "82") (name "unconnected-(U2-P0.27{slash}SCL-Pad2)") (class "Default")
      (node (ref "U2") (pin "2") (pinfunction "P0.27/SCL_2") (pintype "bidirectional"))
    )
    (net (code "83") (name "unconnected-(U2-P0.28{slash}AIN4-PadA1)") (class "Default")
      (node (ref "U2") (pin "A1") (pinfunction "P0.28/AIN4_A1") (pintype "bidirectional"))
    )
    (net (code "84") (name "unconnected-(U2-P0.29{slash}AIN5-PadA2)") (class "Default")
      (node (ref "U2") (pin "A2") (pinfunction "P0.29/AIN5_A2") (pintype "bidirectional"))
    )
    (net (code "85") (name "unconnected-(U2-P0.30{slash}AIN6-PadB2)") (class "Default")
      (node (ref "U2") (pin "B2") (pinfunction "P0.30/AIN6_B2") (pintype "bidirectional"))
    )
    (net (code "86") (name "unconnected-(U2-P0.31{slash}AIN7-PadB3)") (class "Default")
      (node (ref "U2") (pin "B3") (pinfunction "P0.31/AIN7_B3") (pintype "bidirectional"))
    )
    (net (code "87") (name "unconnected-(U2-P1.00-Pad12)") (class "Default")
      (node (ref "U2") (pin "12") (pinfunction "P1.00_12") (pintype "bidirectional"))
    )
    (net (code "88") (name "unconnected-(U2-P1.01-PadD5)") (class "Default")
      (node (ref "U2") (pin "D5") (pinfunction "P1.01_D5") (pintype "bidirectional"))
    )
    (net (code "89") (name "unconnected-(U2-P1.02-PadC5)") (class "Default")
      (node (ref "U2") (pin "C5") (pinfunction "P1.02_C5") (pintype "bidirectional"))
    )
    (net (code "90") (name "unconnected-(U2-P1.03-PadB6)") (class "Default")
      (node (ref "U2") (pin "B6") (pinfunction "P1.03_B6") (pintype "bidirectional"))
    )
    (net (code "91") (name "unconnected-(U2-P1.04-PadC6)") (class "Default")
      (node (ref "U2") (pin "C6") (pinfunction "P1.04_C6") (pintype "bidirectional"))
    )
    (net (code "92") (name "unconnected-(U2-P1.05-PadD6)") (class "Default")
      (node (ref "U2") (pin "D6") (pinfunction "P1.05_D6") (pintype "bidirectional"))
    )
    (net (code "93") (name "unconnected-(U2-P1.06-PadZ6)") (class "Default")
      (node (ref "U2") (pin "Z6") (pinfunction "P1.06_Z6") (pintype "bidirectional"))
    )
    (net (code "94") (name "unconnected-(U2-P1.07-PadE0)") (class "Default")
      (node (ref "U2") (pin "E0") (pinfunction "P1.07_E0") (pintype "bidirectional"))
    )
    (net (code "95") (name "unconnected-(U2-P1.08-PadA6)") (class "Default")
      (node (ref "U2") (pin "A6") (pinfunction "P1.08_A6") (pintype "bidirectional"))
    )
    (net (code "96") (name "unconnected-(U2-P1.09-PadE3)") (class "Default")
      (node (ref "U2") (pin "E3") (pinfunction "P1.09_E3") (pintype "bidirectional"))
    )
    (net (code "97") (name "unconnected-(U2-P1.10-PadZ5)") (class "Default")
      (node (ref "U2") (pin "Z5") (pinfunction "P1.10_Z5") (pintype "bidirectional"))
    )
    (net (code "98") (name "unconnected-(U2-P1.11-PadZ0)") (class "Default")
      (node (ref "U2") (pin "Z0") (pinfunction "P1.11_Z0") (pintype "bidirectional"))
    )
    (net (code "99") (name "unconnected-(U2-P1.12-PadZ1)") (class "Default")
      (node (ref "U2") (pin "Z1") (pinfunction "P1.12_Z1") (pintype "bidirectional"))
    )
    (net (code "100") (name "unconnected-(U2-P1.13-PadZ2)") (class "Default")
      (node (ref "U2") (pin "Z2") (pinfunction "P1.13_Z2") (pintype "bidirectional"))
    )
    (net (code "101") (name "unconnected-(U2-P1.14-PadZ3)") (class "Default")
      (node (ref "U2") (pin "Z3") (pinfunction "P1.14_Z3") (pintype "bidirectional"))
    )
    (net (code "102") (name "unconnected-(U2-P1.15-PadZ4)") (class "Default")
      (node (ref "U2") (pin "Z4") (pinfunction "P1.15_Z4") (pintype "bidirectional"))
    )
    (net (code "103") (name "unconnected-(U2-VBUS-PadF6)") (class "Default")
      (node (ref "U2") (pin "F6") (pinfunction "VBUS_F6") (pintype "power_in"))
    )
    (net (code "104") (name "unconnected-(U3-CTS-Pad15)") (class "Default")
      (node (ref "U3") (pin "15") (pinfunction "CTS_15") (pintype "bidirectional"))
    )
    (net (code "105") (name "unconnected-(U3-GPIO0{slash}CLK-Pad2)") (class "Default")
      (node (ref "U3") (pin "2") (pinfunction "GPIO0/CLK_2") (pintype "bidirectional"))
    )
    (net (code "106") (name "unconnected-(U3-GPIO1{slash}485-Pad1)") (class "Default")
      (node (ref "U3") (pin "1") (pinfunction "GPIO1/485_1") (pintype "bidirectional"))
    )
    (net (code "107") (name "unconnected-(U3-GPIO2{slash}TXT-Pad20)") (class "Default")
      (node (ref "U3") (pin "20") (pinfunction "GPIO2/TXT_20") (pintype "bidirectional"))
    )
    (net (code "108") (name "unconnected-(U3-GPIO3{slash}RXT-Pad19)") (class "Default")
      (node (ref "U3") (pin "19") (pinfunction "GPIO3/RXT_19") (pintype "bidirectional"))
    )
    (net (code "109") (name "unconnected-(U3-RTS-Pad16)") (class "Default")
      (node (ref "U3") (pin "16") (pinfunction "RTS_16") (pintype "bidirectional"))
    )
    (net (code "110") (name "unconnected-(U3-SUSPEND-Pad14)") (class "Default")
      (node (ref "U3") (pin "14") (pinfunction "SUSPEND_14") (pintype "bidirectional"))
    )
    (net (code "111") (name "unconnected-(U3-WAKEUP-Pad13)") (class "Default")
      (node (ref "U3") (pin "13") (pinfunction "WAKEUP_13") (pintype "bidirectional"))
    )
    (net (code "112") (name "unconnected-(U3-~{SUSPEND}-Pad11)") (class "Default")
      (node (ref "U3") (pin "11") (pinfunction "~{SUSPEND}_11") (pintype "bidirectional"))
    )
    (net (code "113") (name "unconnected-(U5-IO21-Pad33)") (class "Default")
      (node (ref "U5") (pin "33") (pinfunction "IO21_33") (pintype "bidirectional"))
    )
    (net (code "114") (name "unconnected-(U5-SENSOR_VN-Pad5)") (class "Default")
      (node (ref "U5") (pin "5") (pinfunction "SENSOR_VN_5") (pintype "bidirectional"))
    )
    (net (code "115") (name "unconnected-(U5-SENSOR_VP-Pad4)") (class "Default")
      (node (ref "U5") (pin "4") (pinfunction "SENSOR_VP_4") (pintype "bidirectional"))
    )
    (net (code "116") (name "unconnected-(U6-IO21-Pad33)") (class "Default")
      (node (ref "U6") (pin "33") (pinfunction "IO21_33") (pintype "bidirectional"))
    )
    (net (code "117") (name "unconnected-(U6-SENSOR_VN-Pad5)") (class "Default")
      (node (ref "U6") (pin "5") (pinfunction "SENSOR_VN_5") (pintype "bidirectional"))
    )
    (net (code "118") (name "unconnected-(U6-SENSOR_VP-Pad4)") (class "Default")
      (node (ref "U6") (pin "4") (pinfunction "SENSOR_VP_4") (pintype "bidirectional"))
    )
    (net (code "119") (name "~{NRF_RESET}") (class "Default")
      (node (ref "J2") (pin "3") (pinfunction "~{RESET}_3") (pintype "bidirectional"))
      (node (ref "U2") (pin "14") (pinfunction "P0.18/RESET_14") (pintype "bidirectional"))
      (node (ref "U5") (pin "36") (pinfunction "IO22_36") (pintype "bidirectional"))
      (node (ref "U6") (pin "36") (pinfunction "IO22_36") (pintype "bidirectional"))
    )
    (net (code "120") (name "~{SD_INSERTED}") (class "Default")
      (node (ref "D1") (pin "P$1") (pinfunction "CATHODE_P$1") (pintype "bidirectional"))
      (node (ref "J1") (pin "SW-B") (pinfunction "B_SW-B") (pintype "bidirectional"))
      (node (ref "R11") (pin "2") (pinfunction "2_2") (pintype "passive"))
      (node (ref "U5") (pin "12") (pinfunction "IO27_12") (pintype "bidirectional"))
      (node (ref "U6") (pin "12") (pinfunction "IO27_12") (pintype "bidirectional"))
    )
  )
)
